# mainboard.net
KiCad netlist of a schematic drawn in EAGLE
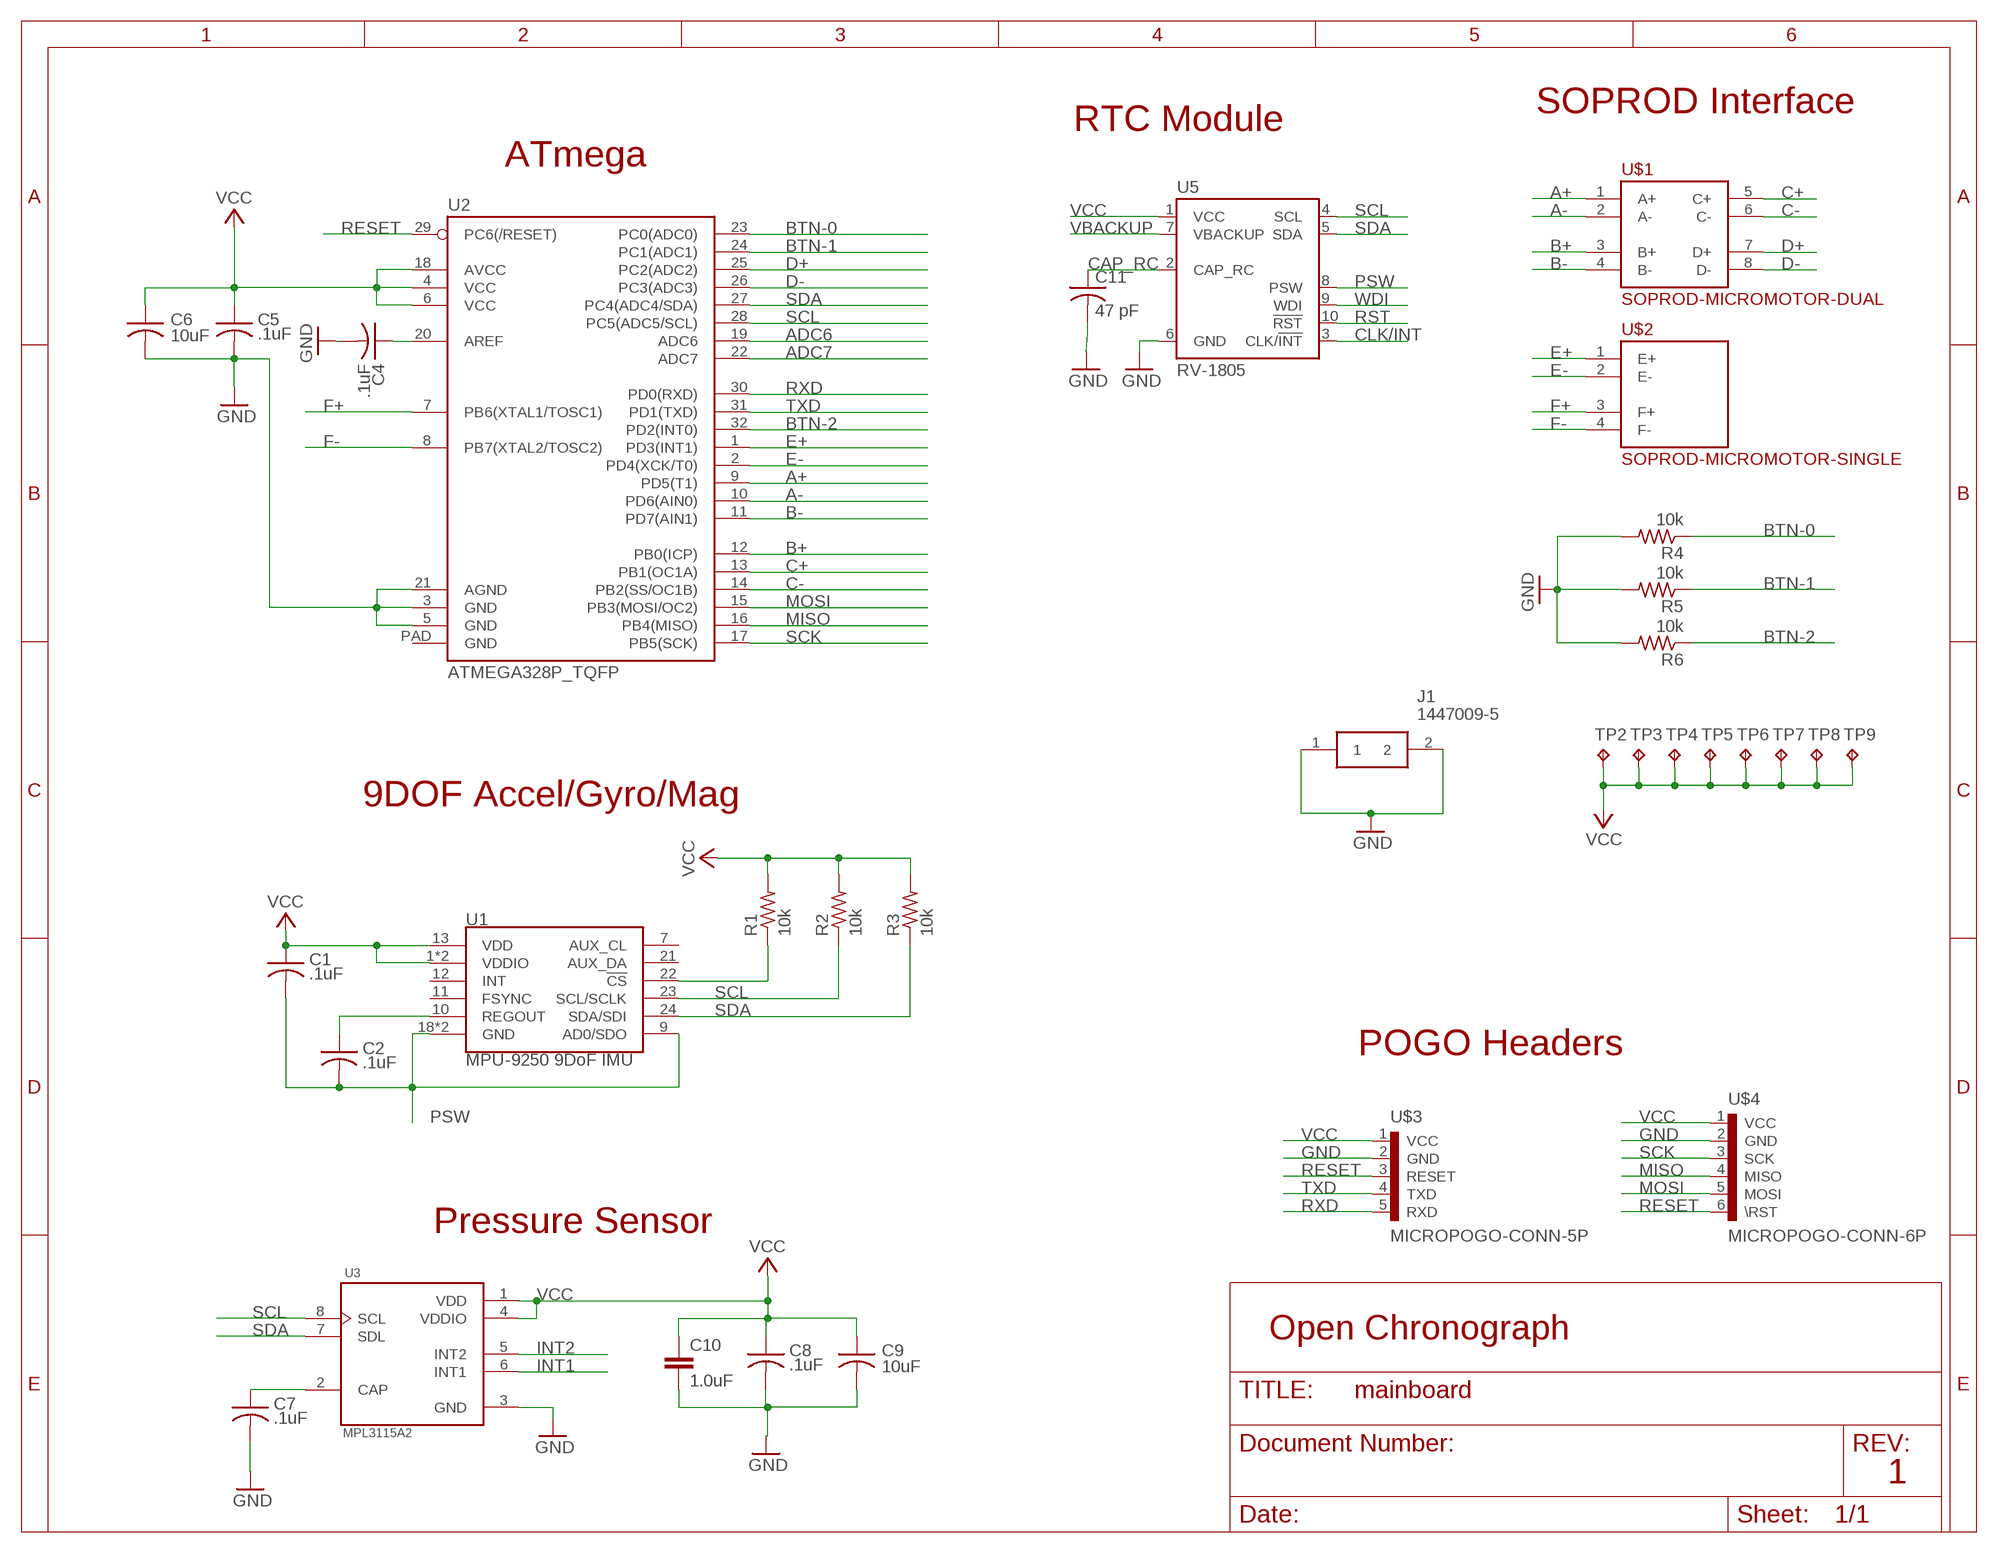
[diagram p0: schematic, sheet 1]

(export (version "E")
  (design (tool "Eeschema 10.0.6"))
  (components
    (comp (ref "C1")
      (value ".1uF")
      (footprint "eagle-import:C0402")
      (fields (field (name "PARTNO") "AS-ITM-00008"))
      (libsource (lib "eagle-import") (part "AS-ITM-00008"))
    )
    (comp (ref "C2")
      (value ".1uF")
      (footprint "eagle-import:C0402")
      (fields (field (name "PARTNO") "AS-ITM-00008"))
      (libsource (lib "eagle-import") (part "AS-ITM-00008"))
    )
    (comp (ref "C4")
      (value ".1uF")
      (footprint "eagle-import:C0402")
      (fields (field (name "PARTNO") "AS-ITM-00008"))
      (libsource (lib "eagle-import") (part "AS-ITM-00008"))
    )
    (comp (ref "C5")
      (value ".1uF")
      (footprint "eagle-import:C0402")
      (fields (field (name "PARTNO") "AS-ITM-00008"))
      (libsource (lib "eagle-import") (part "AS-ITM-00008"))
    )
    (comp (ref "C6")
      (value "10uF")
      (footprint "eagle-import:C0603")
      (fields (field (name "PARTNO") "AS-ITM-00002"))
      (libsource (lib "eagle-import") (part "AS-ITM-00002"))
    )
    (comp (ref "C7")
      (value ".1uF")
      (footprint "eagle-import:C0402")
      (fields (field (name "PARTNO") "AS-ITM-00008"))
      (libsource (lib "eagle-import") (part "AS-ITM-00008"))
    )
    (comp (ref "C8")
      (value ".1uF")
      (footprint "eagle-import:C0402")
      (fields (field (name "PARTNO") "AS-ITM-00008"))
      (libsource (lib "eagle-import") (part "AS-ITM-00008"))
    )
    (comp (ref "C9")
      (value "10uF")
      (footprint "eagle-import:C0603")
      (fields (field (name "PARTNO") "AS-ITM-00002"))
      (libsource (lib "eagle-import") (part "AS-ITM-00002"))
    )
    (comp (ref "C10")
      (value "1.0uF")
      (footprint "eagle-import:0402")
      (libsource (lib "eagle-import") (part "1.0UF-0402-16V-10%"))
    )
    (comp (ref "C11")
      (value "47 pF")
      (footprint "eagle-import:C0402")
      (libsource (lib "eagle-import") (part "C-USC0402"))
    )
    (comp (ref "J1")
      (value "1447009-5")
      (footprint "eagle-import:14470095")
      (fields (field (name "MOUSER_PART_NUMBER") "571-1447009-5"))
      (libsource (lib "eagle-import") (part "1447009-5"))
    )
    (comp (ref "R1")
      (value "10k")
      (footprint "eagle-import:R0402")
      (libsource (lib "eagle-import") (part "R-US_R0402"))
    )
    (comp (ref "R2")
      (value "10k")
      (footprint "eagle-import:R0402")
      (libsource (lib "eagle-import") (part "R-US_R0402"))
    )
    (comp (ref "R3")
      (value "10k")
      (footprint "eagle-import:R0402")
      (libsource (lib "eagle-import") (part "R-US_R0402"))
    )
    (comp (ref "R4")
      (value "10k")
      (footprint "eagle-import:R0402")
      (libsource (lib "eagle-import") (part "R-US_R0402"))
    )
    (comp (ref "R5")
      (value "10k")
      (footprint "eagle-import:R0402")
      (libsource (lib "eagle-import") (part "R-US_R0402"))
    )
    (comp (ref "R6")
      (value "10k")
      (footprint "eagle-import:R0402")
      (libsource (lib "eagle-import") (part "R-US_R0402"))
    )
    (comp (ref "TP2")
      (value "TPTP15SQ")
      (footprint "eagle-import:TP15SQ")
      (libsource (lib "eagle-import") (part "TPTP15SQ"))
    )
    (comp (ref "TP3")
      (value "TPTP15SQ")
      (footprint "eagle-import:TP15SQ")
      (libsource (lib "eagle-import") (part "TPTP15SQ"))
    )
    (comp (ref "TP4")
      (value "TPTP15SQ")
      (footprint "eagle-import:TP15SQ")
      (libsource (lib "eagle-import") (part "TPTP15SQ"))
    )
    (comp (ref "TP5")
      (value "TPTP15SQ")
      (footprint "eagle-import:TP15SQ")
      (libsource (lib "eagle-import") (part "TPTP15SQ"))
    )
    (comp (ref "TP6")
      (value "TPTP15SQ")
      (footprint "eagle-import:TP15SQ")
      (libsource (lib "eagle-import") (part "TPTP15SQ"))
    )
    (comp (ref "TP7")
      (value "TPTP15SQ")
      (footprint "eagle-import:TP15SQ")
      (libsource (lib "eagle-import") (part "TPTP15SQ"))
    )
    (comp (ref "TP8")
      (value "TPTP15SQ")
      (footprint "eagle-import:TP15SQ")
      (libsource (lib "eagle-import") (part "TPTP15SQ"))
    )
    (comp (ref "TP9")
      (value "TPTP15SQ")
      (footprint "eagle-import:TP15SQ")
      (libsource (lib "eagle-import") (part "TPTP15SQ"))
    )
    (comp (ref "U$1")
      (value "SOPROD-MICROMOTOR-DUAL")
      (footprint "eagle-import:SOPROD-DUAL")
      (libsource (lib "eagle-import") (part "SOPROD-MICROMOTOR-DUAL"))
    )
    (comp (ref "U$2")
      (value "SOPROD-MICROMOTOR-SINGLE")
      (footprint "eagle-import:SOPROD-SINGLE")
      (libsource (lib "eagle-import") (part "SOPROD-MICROMOTOR-SINGLE"))
    )
    (comp (ref "U$3")
      (value "MICROPOGO-CONN-5P")
      (footprint "eagle-import:MICROPOGO-CONN-5P-ASYM")
      (libsource (lib "eagle-import") (part "MICROPOGO-CONN-5P"))
    )
    (comp (ref "U$4")
      (value "MICROPOGO-CONN-6P")
      (footprint "eagle-import:MICROPOGO-CONN-6P-ASYM")
      (libsource (lib "eagle-import") (part "MICROPOGO-CONN-6P"))
    )
    (comp (ref "U1")
      (value "MPU-9250 9DoF IMU")
      (footprint "eagle-import:QFN24-3X3")
      (libsource (lib "eagle-import") (part "MPU-9250"))
    )
    (comp (ref "U2")
      (value "ATMEGA328P_TQFP")
      (footprint "eagle-import:MLF32-PAD")
      (libsource (lib "eagle-import") (part "ATMEGA328P_MLFMLF32"))
    )
    (comp (ref "U3")
      (value "MPL3115A2")
      (footprint "eagle-import:PSON125P300X500X120-8N")
      (fields (field (name "MANUFACTURER") "Freescale Semiconductor"))
      (libsource (lib "eagle-import") (part "MPL3115A2"))
    )
    (comp (ref "U5")
      (value "RV-1805")
      (footprint "eagle-import:RV-1805")
      (libsource (lib "eagle-import") (part "RV-1805"))
    )
  )
  (nets
    (net (code "1") (name "/A+") (class "Default")
      (node (ref "U$1") (pin "1") (pinfunction "A+_1") (pintype "bidirectional"))
      (node (ref "U2") (pin "9") (pinfunction "PD5(T1)_9") (pintype "bidirectional"))
    )
    (net (code "2") (name "/A-") (class "Default")
      (node (ref "U$1") (pin "2") (pinfunction "A-_2") (pintype "bidirectional"))
      (node (ref "U2") (pin "10") (pinfunction "PD6(AIN0)_10") (pintype "bidirectional"))
    )
    (net (code "3") (name "/ADC6") (class "Default")
      (node (ref "U2") (pin "19") (pinfunction "ADC6_19") (pintype "bidirectional"))
    )
    (net (code "4") (name "/ADC7") (class "Default")
      (node (ref "U2") (pin "22") (pinfunction "ADC7_22") (pintype "bidirectional"))
    )
    (net (code "5") (name "/B+") (class "Default")
      (node (ref "U$1") (pin "3") (pinfunction "B+_3") (pintype "bidirectional"))
      (node (ref "U2") (pin "12") (pinfunction "PB0(ICP)_12") (pintype "bidirectional"))
    )
    (net (code "6") (name "/B-") (class "Default")
      (node (ref "U$1") (pin "4") (pinfunction "B-_4") (pintype "bidirectional"))
      (node (ref "U2") (pin "11") (pinfunction "PD7(AIN1)_11") (pintype "bidirectional"))
    )
    (net (code "7") (name "/BTN-0") (class "Default")
      (node (ref "R4") (pin "1") (pinfunction "1_1") (pintype "passive"))
      (node (ref "U2") (pin "23") (pinfunction "PC0(ADC0)_23") (pintype "bidirectional"))
    )
    (net (code "8") (name "/BTN-1") (class "Default")
      (node (ref "R5") (pin "1") (pinfunction "1_1") (pintype "passive"))
      (node (ref "U2") (pin "24") (pinfunction "PC1(ADC1)_24") (pintype "bidirectional"))
    )
    (net (code "9") (name "/BTN-2") (class "Default")
      (node (ref "R6") (pin "1") (pinfunction "1_1") (pintype "passive"))
      (node (ref "U2") (pin "32") (pinfunction "PD2(INT0)_32") (pintype "bidirectional"))
    )
    (net (code "10") (name "/C+") (class "Default")
      (node (ref "U$1") (pin "5") (pinfunction "C+_5") (pintype "bidirectional"))
      (node (ref "U2") (pin "13") (pinfunction "PB1(OC1A)_13") (pintype "bidirectional"))
    )
    (net (code "11") (name "/C-") (class "Default")
      (node (ref "U$1") (pin "6") (pinfunction "C-_6") (pintype "bidirectional"))
      (node (ref "U2") (pin "14") (pinfunction "PB2(SS/OC1B)_14") (pintype "bidirectional"))
    )
    (net (code "12") (name "/CAP_RC") (class "Default")
      (node (ref "C11") (pin "1") (pinfunction "1_1") (pintype "passive"))
      (node (ref "U5") (pin "2") (pinfunction "CAP_RC_2") (pintype "bidirectional"))
    )
    (net (code "13") (name "/CLK{slash}INT") (class "Default")
      (node (ref "U5") (pin "3") (pinfunction "CLK/~{INT}_3") (pintype "bidirectional"))
    )
    (net (code "14") (name "/D+") (class "Default")
      (node (ref "U$1") (pin "7") (pinfunction "D+_7") (pintype "bidirectional"))
      (node (ref "U2") (pin "25") (pinfunction "PC2(ADC2)_25") (pintype "bidirectional"))
    )
    (net (code "15") (name "/D-") (class "Default")
      (node (ref "U$1") (pin "8") (pinfunction "D-_8") (pintype "bidirectional"))
      (node (ref "U2") (pin "26") (pinfunction "PC3(ADC3)_26") (pintype "bidirectional"))
    )
    (net (code "16") (name "/E+") (class "Default")
      (node (ref "U$2") (pin "1") (pinfunction "E+_1") (pintype "bidirectional"))
      (node (ref "U2") (pin "1") (pinfunction "PD3(INT1)_1") (pintype "bidirectional"))
    )
    (net (code "17") (name "/E-") (class "Default")
      (node (ref "U$2") (pin "2") (pinfunction "E-_2") (pintype "bidirectional"))
      (node (ref "U2") (pin "2") (pinfunction "PD4(XCK/T0)_2") (pintype "bidirectional"))
    )
    (net (code "18") (name "/F+") (class "Default")
      (node (ref "U$2") (pin "3") (pinfunction "F+_3") (pintype "bidirectional"))
      (node (ref "U2") (pin "7") (pinfunction "PB6(XTAL1/TOSC1)_7") (pintype "bidirectional"))
    )
    (net (code "19") (name "/F-") (class "Default")
      (node (ref "U$2") (pin "4") (pinfunction "F-_4") (pintype "bidirectional"))
      (node (ref "U2") (pin "8") (pinfunction "PB7(XTAL2/TOSC2)_8") (pintype "bidirectional"))
    )
    (net (code "20") (name "/INT1") (class "Default")
      (node (ref "U3") (pin "6") (pinfunction "INT1_6") (pintype "output"))
    )
    (net (code "21") (name "/INT2") (class "Default")
      (node (ref "U3") (pin "5") (pinfunction "INT2_5") (pintype "output"))
    )
    (net (code "22") (name "/MISO") (class "Default")
      (node (ref "U$4") (pin "4") (pinfunction "MISO_4") (pintype "bidirectional"))
      (node (ref "U2") (pin "16") (pinfunction "PB4(MISO)_16") (pintype "bidirectional"))
    )
    (net (code "23") (name "/MOSI") (class "Default")
      (node (ref "U$4") (pin "5") (pinfunction "MOSI_5") (pintype "bidirectional"))
      (node (ref "U2") (pin "15") (pinfunction "PB3(MOSI/OC2)_15") (pintype "bidirectional"))
    )
    (net (code "24") (name "/PSW") (class "Default")
      (node (ref "C1") (pin "2") (pinfunction "2_2") (pintype "passive"))
      (node (ref "C2") (pin "2") (pinfunction "2_2") (pintype "passive"))
      (node (ref "U1") (pin "18") (pinfunction "GND_18") (pintype "bidirectional"))
      (node (ref "U1") (pin "20") (pinfunction "GND_20") (pintype "bidirectional"))
      (node (ref "U1") (pin "9") (pinfunction "AD0/SDO_9") (pintype "bidirectional"))
      (node (ref "U5") (pin "8") (pinfunction "PSW_8") (pintype "bidirectional"))
    )
    (net (code "25") (name "/RESET") (class "Default")
      (node (ref "U$3") (pin "3") (pinfunction "RESET_3") (pintype "bidirectional"))
      (node (ref "U$4") (pin "6") (pinfunction "\\RST_6") (pintype "bidirectional"))
      (node (ref "U2") (pin "29") (pinfunction "PC6(/RESET)_29") (pintype "bidirectional"))
    )
    (net (code "26") (name "/RST") (class "Default")
      (node (ref "U5") (pin "10") (pinfunction "~{RST}_10") (pintype "bidirectional"))
    )
    (net (code "27") (name "/RXD") (class "Default")
      (node (ref "U$3") (pin "5") (pinfunction "RXD_5") (pintype "bidirectional"))
      (node (ref "U2") (pin "30") (pinfunction "PD0(RXD)_30") (pintype "bidirectional"))
    )
    (net (code "28") (name "/SCK") (class "Default")
      (node (ref "U$4") (pin "3") (pinfunction "SCK_3") (pintype "bidirectional"))
      (node (ref "U2") (pin "17") (pinfunction "PB5(SCK)_17") (pintype "bidirectional"))
    )
    (net (code "29") (name "/SCL") (class "Default")
      (node (ref "R2") (pin "1") (pinfunction "1_1") (pintype "passive"))
      (node (ref "U1") (pin "23") (pinfunction "SCL/SCLK_23") (pintype "bidirectional"))
      (node (ref "U2") (pin "28") (pinfunction "PC5(ADC5/SCL)_28") (pintype "bidirectional"))
      (node (ref "U3") (pin "8") (pinfunction "SCL_8") (pintype "input"))
      (node (ref "U5") (pin "4") (pinfunction "SCL_4") (pintype "bidirectional"))
    )
    (net (code "30") (name "/SDA") (class "Default")
      (node (ref "R3") (pin "1") (pinfunction "1_1") (pintype "passive"))
      (node (ref "U1") (pin "24") (pinfunction "SDA/SDI_24") (pintype "bidirectional"))
      (node (ref "U2") (pin "27") (pinfunction "PC4(ADC4/SDA)_27") (pintype "bidirectional"))
      (node (ref "U3") (pin "7") (pinfunction "SDL_7") (pintype "bidirectional"))
      (node (ref "U5") (pin "5") (pinfunction "SDA_5") (pintype "bidirectional"))
    )
    (net (code "31") (name "/TXD") (class "Default")
      (node (ref "U$3") (pin "4") (pinfunction "TXD_4") (pintype "bidirectional"))
      (node (ref "U2") (pin "31") (pinfunction "PD1(TXD)_31") (pintype "bidirectional"))
    )
    (net (code "32") (name "/VBACKUP") (class "Default")
      (node (ref "U5") (pin "7") (pinfunction "VBACKUP_7") (pintype "bidirectional"))
    )
    (net (code "33") (name "/WDI") (class "Default")
      (node (ref "U5") (pin "9") (pinfunction "WDI_9") (pintype "bidirectional"))
    )
    (net (code "34") (name "GND") (class "Default")
      (node (ref "C10") (pin "2") (pinfunction "2_2") (pintype "passive"))
      (node (ref "C11") (pin "2") (pinfunction "2_2") (pintype "passive"))
      (node (ref "C4") (pin "2") (pinfunction "2_2") (pintype "passive"))
      (node (ref "C5") (pin "2") (pinfunction "2_2") (pintype "passive"))
      (node (ref "C6") (pin "2") (pinfunction "2_2") (pintype "passive"))
      (node (ref "C7") (pin "2") (pinfunction "2_2") (pintype "passive"))
      (node (ref "C8") (pin "2") (pinfunction "2_2") (pintype "passive"))
      (node (ref "C9") (pin "2") (pinfunction "2_2") (pintype "passive"))
      (node (ref "J1") (pin "1") (pinfunction "1_1") (pintype "bidirectional"))
      (node (ref "J1") (pin "2") (pinfunction "2_2") (pintype "bidirectional"))
      (node (ref "R4") (pin "2") (pinfunction "2_2") (pintype "passive"))
      (node (ref "R5") (pin "2") (pinfunction "2_2") (pintype "passive"))
      (node (ref "R6") (pin "2") (pinfunction "2_2") (pintype "passive"))
      (node (ref "U$3") (pin "2") (pinfunction "GND_2") (pintype "bidirectional"))
      (node (ref "U$4") (pin "2") (pinfunction "GND_2") (pintype "bidirectional"))
      (node (ref "U2") (pin "21") (pinfunction "AGND_21") (pintype "bidirectional"))
      (node (ref "U2") (pin "3") (pinfunction "GND_3") (pintype "bidirectional"))
      (node (ref "U2") (pin "5") (pinfunction "GND_5") (pintype "bidirectional"))
      (node (ref "U3") (pin "3") (pinfunction "GND_3") (pintype "power_in"))
      (node (ref "U5") (pin "6") (pinfunction "GND_6") (pintype "bidirectional"))
    )
    (net (code "35") (name "Net-(U1-REGOUT)") (class "Default")
      (node (ref "C2") (pin "1") (pinfunction "1_1") (pintype "passive"))
      (node (ref "U1") (pin "10") (pinfunction "REGOUT_10") (pintype "bidirectional"))
    )
    (net (code "36") (name "Net-(U1-~{CS})") (class "Default")
      (node (ref "R1") (pin "1") (pinfunction "1_1") (pintype "passive"))
      (node (ref "U1") (pin "22") (pinfunction "~{CS}_22") (pintype "bidirectional"))
    )
    (net (code "37") (name "Net-(U2-AREF)") (class "Default")
      (node (ref "C4") (pin "1") (pinfunction "1_1") (pintype "passive"))
      (node (ref "U2") (pin "20") (pinfunction "AREF_20") (pintype "bidirectional"))
    )
    (net (code "38") (name "Net-(U3-CAP)") (class "Default")
      (node (ref "C7") (pin "1") (pinfunction "1_1") (pintype "passive"))
      (node (ref "U3") (pin "2") (pinfunction "CAP_2") (pintype "bidirectional"))
    )
    (net (code "39") (name "VCC") (class "Default")
      (node (ref "C1") (pin "1") (pinfunction "1_1") (pintype "passive"))
      (node (ref "C10") (pin "1") (pinfunction "1_1") (pintype "passive"))
      (node (ref "C5") (pin "1") (pinfunction "1_1") (pintype "passive"))
      (node (ref "C6") (pin "1") (pinfunction "1_1") (pintype "passive"))
      (node (ref "C8") (pin "1") (pinfunction "1_1") (pintype "passive"))
      (node (ref "C9") (pin "1") (pinfunction "1_1") (pintype "passive"))
      (node (ref "R1") (pin "2") (pinfunction "2_2") (pintype "passive"))
      (node (ref "R2") (pin "2") (pinfunction "2_2") (pintype "passive"))
      (node (ref "R3") (pin "2") (pinfunction "2_2") (pintype "passive"))
      (node (ref "TP2") (pin "TP") (pinfunction "TP_TP") (pintype "input"))
      (node (ref "TP3") (pin "TP") (pinfunction "TP_TP") (pintype "input"))
      (node (ref "TP4") (pin "TP") (pinfunction "TP_TP") (pintype "input"))
      (node (ref "TP5") (pin "TP") (pinfunction "TP_TP") (pintype "input"))
      (node (ref "TP6") (pin "TP") (pinfunction "TP_TP") (pintype "input"))
      (node (ref "TP7") (pin "TP") (pinfunction "TP_TP") (pintype "input"))
      (node (ref "TP8") (pin "TP") (pinfunction "TP_TP") (pintype "input"))
      (node (ref "TP9") (pin "TP") (pinfunction "TP_TP") (pintype "input"))
      (node (ref "U$3") (pin "1") (pinfunction "VCC_1") (pintype "bidirectional"))
      (node (ref "U$4") (pin "1") (pinfunction "VCC_1") (pintype "bidirectional"))
      (node (ref "U1") (pin "1") (pinfunction "VDDIO_1") (pintype "bidirectional"))
      (node (ref "U1") (pin "13") (pinfunction "VDD_13") (pintype "bidirectional"))
      (node (ref "U1") (pin "8") (pinfunction "VDDIO_8") (pintype "bidirectional"))
      (node (ref "U2") (pin "18") (pinfunction "AVCC_18") (pintype "bidirectional"))
      (node (ref "U2") (pin "4") (pinfunction "VCC_4") (pintype "bidirectional"))
      (node (ref "U2") (pin "6") (pinfunction "VCC_6") (pintype "bidirectional"))
      (node (ref "U3") (pin "1") (pinfunction "VDD_1") (pintype "power_in"))
      (node (ref "U3") (pin "4") (pinfunction "VDDIO_4") (pintype "power_in"))
      (node (ref "U5") (pin "1") (pinfunction "VCC_1") (pintype "bidirectional"))
    )
    (net (code "40") (name "unconnected-(U1-AUX_CL-Pad7)") (class "Default")
      (node (ref "U1") (pin "7") (pinfunction "AUX_CL_7") (pintype "bidirectional"))
    )
    (net (code "41") (name "unconnected-(U1-AUX_DA-Pad21)") (class "Default")
      (node (ref "U1") (pin "21") (pinfunction "AUX_DA_21") (pintype "bidirectional"))
    )
    (net (code "42") (name "unconnected-(U1-FSYNC-Pad11)") (class "Default")
      (node (ref "U1") (pin "11") (pinfunction "FSYNC_11") (pintype "bidirectional"))
    )
    (net (code "43") (name "unconnected-(U1-INT-Pad12)") (class "Default")
      (node (ref "U1") (pin "12") (pinfunction "INT_12") (pintype "bidirectional"))
    )
    (net (code "44") (name "unconnected-(U2-GND-PadPAD)") (class "Default")
      (node (ref "U2") (pin "PAD") (pinfunction "GND_PAD") (pintype "bidirectional"))
    )
  )
)
